# DIP2350.net
KiCad netlist of a schematic drawn in Altium Designer
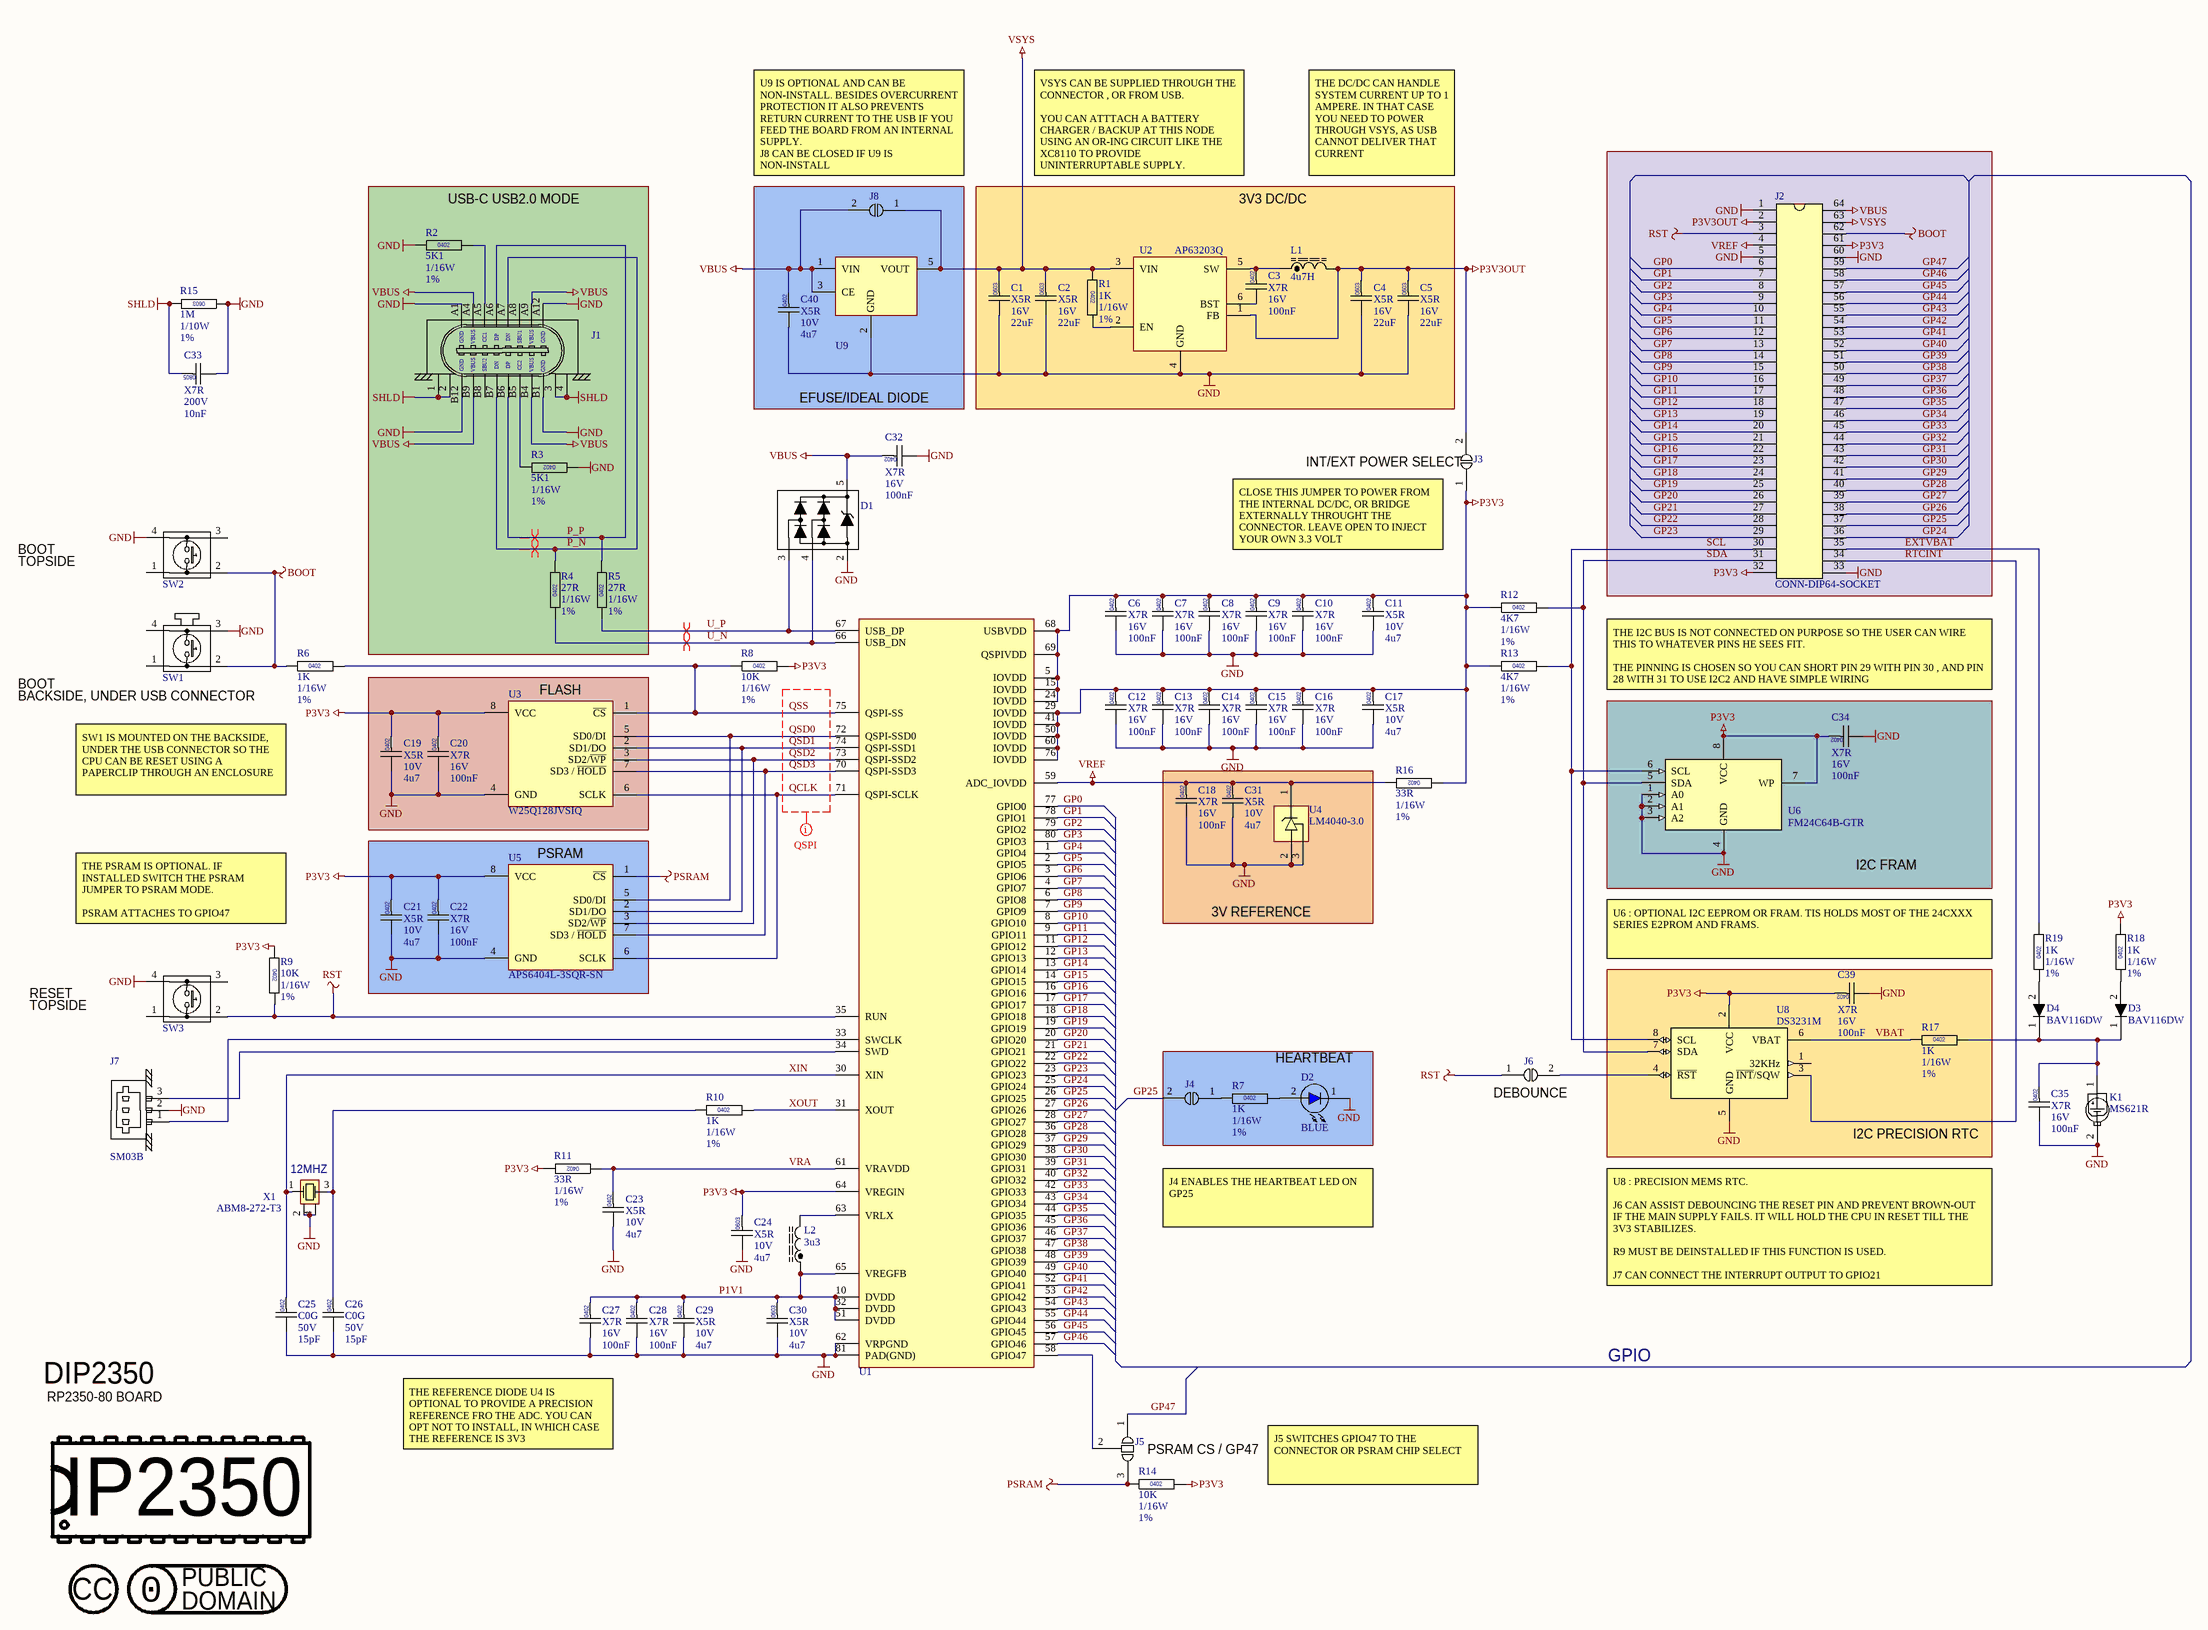
[diagram p0: DIP2350.SchDoc]

(export (version "E")
  (design (tool "Eeschema 10.0.6"))
  (components
    (comp (ref "C1")
      (value "CAP0603")
      (footprint "CAPC0603")
      (description "CAPACITOR,CERAMIC,22uF,16V,X5R,0603")
      (fields
        (field (name "DIELECTRIC") "X5R")
        (field (name "VOLTAGE") "16V")
        (field (name "CAPACITANCE") "22uF")
      )
      (libsource (lib "CAPACITORS") (part "CAPC-0603-22uF-16V-X5R"))
    )
    (comp (ref "C2")
      (value "CAP0603")
      (footprint "CAPC0603")
      (description "CAPACITOR,CERAMIC,22uF,16V,X5R,0603")
      (fields
        (field (name "DIELECTRIC") "X5R")
        (field (name "VOLTAGE") "16V")
        (field (name "CAPACITANCE") "22uF")
      )
      (libsource (lib "CAPACITORS") (part "CAPC-0603-22uF-16V-X5R"))
    )
    (comp (ref "C3")
      (value "CAP0402")
      (footprint "CAPC0402")
      (description "CAPACITOR,CERAMIC,100nF,16V,X7R,0402")
      (fields
        (field (name "DIELECTRIC") "X7R")
        (field (name "VOLTAGE") "16V")
        (field (name "CAPACITANCE") "100nF")
      )
      (libsource (lib "CAPACITORS") (part "CAPC-0402-100nF-16V-X7R"))
    )
    (comp (ref "C4")
      (value "CAP0603")
      (footprint "CAPC0603")
      (description "CAPACITOR,CERAMIC,22uF,16V,X5R,0603")
      (fields
        (field (name "DIELECTRIC") "X5R")
        (field (name "VOLTAGE") "16V")
        (field (name "CAPACITANCE") "22uF")
      )
      (libsource (lib "CAPACITORS") (part "CAPC-0603-22uF-16V-X5R"))
    )
    (comp (ref "C5")
      (value "CAP0603")
      (footprint "CAPC0603")
      (description "CAPACITOR,CERAMIC,22uF,16V,X5R,0603")
      (fields
        (field (name "DIELECTRIC") "X5R")
        (field (name "VOLTAGE") "16V")
        (field (name "CAPACITANCE") "22uF")
      )
      (libsource (lib "CAPACITORS") (part "CAPC-0603-22uF-16V-X5R"))
    )
    (comp (ref "C6")
      (value "CAP0402")
      (footprint "CAPC0402")
      (description "CAPACITOR,CERAMIC,100nF,16V,X7R,0402")
      (fields
        (field (name "DIELECTRIC") "X7R")
        (field (name "VOLTAGE") "16V")
        (field (name "CAPACITANCE") "100nF")
      )
      (libsource (lib "CAPACITORS") (part "CAPC-0402-100nF-16V-X7R"))
    )
    (comp (ref "C7")
      (value "CAP0402")
      (footprint "CAPC0402")
      (description "CAPACITOR,CERAMIC,100nF,16V,X7R,0402")
      (fields
        (field (name "DIELECTRIC") "X7R")
        (field (name "VOLTAGE") "16V")
        (field (name "CAPACITANCE") "100nF")
      )
      (libsource (lib "CAPACITORS") (part "CAPC-0402-100nF-16V-X7R"))
    )
    (comp (ref "C8")
      (value "CAP0402")
      (footprint "CAPC0402")
      (description "CAPACITOR,CERAMIC,100nF,16V,X7R,0402")
      (fields
        (field (name "DIELECTRIC") "X7R")
        (field (name "VOLTAGE") "16V")
        (field (name "CAPACITANCE") "100nF")
      )
      (libsource (lib "CAPACITORS") (part "CAPC-0402-100nF-16V-X7R"))
    )
    (comp (ref "C9")
      (value "CAP0402")
      (footprint "CAPC0402")
      (description "CAPACITOR,CERAMIC,100nF,16V,X7R,0402")
      (fields
        (field (name "DIELECTRIC") "X7R")
        (field (name "VOLTAGE") "16V")
        (field (name "CAPACITANCE") "100nF")
      )
      (libsource (lib "CAPACITORS") (part "CAPC-0402-100nF-16V-X7R"))
    )
    (comp (ref "C10")
      (value "CAP0402")
      (footprint "CAPC0402")
      (description "CAPACITOR,CERAMIC,100nF,16V,X7R,0402")
      (fields
        (field (name "DIELECTRIC") "X7R")
        (field (name "VOLTAGE") "16V")
        (field (name "CAPACITANCE") "100nF")
      )
      (libsource (lib "CAPACITORS") (part "CAPC-0402-100nF-16V-X7R"))
    )
    (comp (ref "C11")
      (value "CAP0402")
      (footprint "CAPC0402")
      (description "CAPACITOR,CERAMIC,4u7,10V,X5R,0402")
      (fields
        (field (name "DIELECTRIC") "X5R")
        (field (name "VOLTAGE") "10V")
        (field (name "CAPACITANCE") "4u7")
      )
      (libsource (lib "CAPACITORS") (part "CAPC-0402-4u7-10V-X5R"))
    )
    (comp (ref "C12")
      (value "CAP0402")
      (footprint "CAPC0402")
      (description "CAPACITOR,CERAMIC,100nF,16V,X7R,0402")
      (fields
        (field (name "DIELECTRIC") "X7R")
        (field (name "VOLTAGE") "16V")
        (field (name "CAPACITANCE") "100nF")
      )
      (libsource (lib "CAPACITORS") (part "CAPC-0402-100nF-16V-X7R"))
    )
    (comp (ref "C13")
      (value "CAP0402")
      (footprint "CAPC0402")
      (description "CAPACITOR,CERAMIC,100nF,16V,X7R,0402")
      (fields
        (field (name "DIELECTRIC") "X7R")
        (field (name "VOLTAGE") "16V")
        (field (name "CAPACITANCE") "100nF")
      )
      (libsource (lib "CAPACITORS") (part "CAPC-0402-100nF-16V-X7R"))
    )
    (comp (ref "C14")
      (value "CAP0402")
      (footprint "CAPC0402")
      (description "CAPACITOR,CERAMIC,100nF,16V,X7R,0402")
      (fields
        (field (name "DIELECTRIC") "X7R")
        (field (name "VOLTAGE") "16V")
        (field (name "CAPACITANCE") "100nF")
      )
      (libsource (lib "CAPACITORS") (part "CAPC-0402-100nF-16V-X7R"))
    )
    (comp (ref "C15")
      (value "CAP0402")
      (footprint "CAPC0402")
      (description "CAPACITOR,CERAMIC,100nF,16V,X7R,0402")
      (fields
        (field (name "DIELECTRIC") "X7R")
        (field (name "VOLTAGE") "16V")
        (field (name "CAPACITANCE") "100nF")
      )
      (libsource (lib "CAPACITORS") (part "CAPC-0402-100nF-16V-X7R"))
    )
    (comp (ref "C16")
      (value "CAP0402")
      (footprint "CAPC0402")
      (description "CAPACITOR,CERAMIC,100nF,16V,X7R,0402")
      (fields
        (field (name "DIELECTRIC") "X7R")
        (field (name "VOLTAGE") "16V")
        (field (name "CAPACITANCE") "100nF")
      )
      (libsource (lib "CAPACITORS") (part "CAPC-0402-100nF-16V-X7R"))
    )
    (comp (ref "C17")
      (value "CAP0402")
      (footprint "CAPC0402")
      (description "CAPACITOR,CERAMIC,4u7,10V,X5R,0402")
      (fields
        (field (name "DIELECTRIC") "X5R")
        (field (name "VOLTAGE") "10V")
        (field (name "CAPACITANCE") "4u7")
      )
      (libsource (lib "CAPACITORS") (part "CAPC-0402-4u7-10V-X5R"))
    )
    (comp (ref "C18")
      (value "CAP0402")
      (footprint "CAPC0402")
      (description "CAPACITOR,CERAMIC,100nF,16V,X7R,0402")
      (fields
        (field (name "DIELECTRIC") "X7R")
        (field (name "VOLTAGE") "16V")
        (field (name "CAPACITANCE") "100nF")
      )
      (libsource (lib "CAPACITORS") (part "CAPC-0402-100nF-16V-X7R"))
    )
    (comp (ref "C19")
      (value "CAP0402")
      (footprint "CAPC0402")
      (description "CAPACITOR,CERAMIC,4u7,10V,X5R,0402")
      (fields
        (field (name "DIELECTRIC") "X5R")
        (field (name "VOLTAGE") "10V")
        (field (name "CAPACITANCE") "4u7")
      )
      (libsource (lib "CAPACITORS") (part "CAPC-0402-4u7-10V-X5R"))
    )
    (comp (ref "C20")
      (value "CAP0402")
      (footprint "CAPC0402")
      (description "CAPACITOR,CERAMIC,100nF,16V,X7R,0402")
      (fields
        (field (name "DIELECTRIC") "X7R")
        (field (name "VOLTAGE") "16V")
        (field (name "CAPACITANCE") "100nF")
      )
      (libsource (lib "CAPACITORS") (part "CAPC-0402-100nF-16V-X7R"))
    )
    (comp (ref "C21")
      (value "CAP0402")
      (footprint "CAPC0402")
      (description "CAPACITOR,CERAMIC,4u7,10V,X5R,0402")
      (fields
        (field (name "DIELECTRIC") "X5R")
        (field (name "VOLTAGE") "10V")
        (field (name "CAPACITANCE") "4u7")
      )
      (libsource (lib "CAPACITORS") (part "CAPC-0402-4u7-10V-X5R"))
    )
    (comp (ref "C22")
      (value "CAP0402")
      (footprint "CAPC0402")
      (description "CAPACITOR,CERAMIC,100nF,16V,X7R,0402")
      (fields
        (field (name "DIELECTRIC") "X7R")
        (field (name "VOLTAGE") "16V")
        (field (name "CAPACITANCE") "100nF")
      )
      (libsource (lib "CAPACITORS") (part "CAPC-0402-100nF-16V-X7R"))
    )
    (comp (ref "C23")
      (value "CAP0402")
      (footprint "CAPC0402")
      (description "CAPACITOR,CERAMIC,4u7,10V,X5R,0402")
      (fields
        (field (name "DIELECTRIC") "X5R")
        (field (name "VOLTAGE") "10V")
        (field (name "CAPACITANCE") "4u7")
      )
      (libsource (lib "CAPACITORS") (part "CAPC-0402-4u7-10V-X5R"))
    )
    (comp (ref "C24")
      (value "CAP0603")
      (footprint "CAPC0603")
      (description "CAPACITOR,CERAMIC,4u7,10V,X5R,0603")
      (fields
        (field (name "DIELECTRIC") "X5R")
        (field (name "VOLTAGE") "10V")
        (field (name "CAPACITANCE") "4u7")
      )
      (libsource (lib "CAPACITORS") (part "CAPC-0603-4u7-10V-X5R"))
    )
    (comp (ref "C25")
      (value "CAP0603")
      (footprint "CAPC0402")
      (description "CAPACITOR,CERAMIC,15pF,50V,C0G,0402")
      (fields
        (field (name "DIELECTRIC") "C0G")
        (field (name "VOLTAGE") "50V")
        (field (name "CAPACITANCE") "15pF")
      )
      (libsource (lib "CAPACITORS") (part "CAPC-0402-15PF-50V-C0G"))
    )
    (comp (ref "C26")
      (value "CAP0603")
      (footprint "CAPC0402")
      (description "CAPACITOR,CERAMIC,15pF,50V,C0G,0402")
      (fields
        (field (name "DIELECTRIC") "C0G")
        (field (name "VOLTAGE") "50V")
        (field (name "CAPACITANCE") "15pF")
      )
      (libsource (lib "CAPACITORS") (part "CAPC-0402-15PF-50V-C0G"))
    )
    (comp (ref "C27")
      (value "CAP0402")
      (footprint "CAPC0402")
      (description "CAPACITOR,CERAMIC,100nF,16V,X7R,0402")
      (fields
        (field (name "DIELECTRIC") "X7R")
        (field (name "VOLTAGE") "16V")
        (field (name "CAPACITANCE") "100nF")
      )
      (libsource (lib "CAPACITORS") (part "CAPC-0402-100nF-16V-X7R"))
    )
    (comp (ref "C28")
      (value "CAP0402")
      (footprint "CAPC0402")
      (description "CAPACITOR,CERAMIC,100nF,16V,X7R,0402")
      (fields
        (field (name "DIELECTRIC") "X7R")
        (field (name "VOLTAGE") "16V")
        (field (name "CAPACITANCE") "100nF")
      )
      (libsource (lib "CAPACITORS") (part "CAPC-0402-100nF-16V-X7R"))
    )
    (comp (ref "C29")
      (value "CAP0402")
      (footprint "CAPC0402")
      (description "CAPACITOR,CERAMIC,4u7,10V,X5R,0402")
      (fields
        (field (name "DIELECTRIC") "X5R")
        (field (name "VOLTAGE") "10V")
        (field (name "CAPACITANCE") "4u7")
      )
      (libsource (lib "CAPACITORS") (part "CAPC-0402-4u7-10V-X5R"))
    )
    (comp (ref "C30")
      (value "CAP0603")
      (footprint "CAPC0603")
      (description "CAPACITOR,CERAMIC,4u7,10V,X5R,0603")
      (fields
        (field (name "DIELECTRIC") "X5R")
        (field (name "VOLTAGE") "10V")
        (field (name "CAPACITANCE") "4u7")
      )
      (libsource (lib "CAPACITORS") (part "CAPC-0603-4u7-10V-X5R"))
    )
    (comp (ref "C31")
      (value "CAP0402")
      (footprint "CAPC0402")
      (description "CAPACITOR,CERAMIC,4u7,10V,X5R,0402")
      (fields
        (field (name "DIELECTRIC") "X5R")
        (field (name "VOLTAGE") "10V")
        (field (name "CAPACITANCE") "4u7")
      )
      (libsource (lib "CAPACITORS") (part "CAPC-0402-4u7-10V-X5R"))
    )
    (comp (ref "C32")
      (value "CAP0402")
      (footprint "CAPC0402")
      (description "CAPACITOR,CERAMIC,100nF,16V,X7R,0402")
      (fields
        (field (name "DIELECTRIC") "X7R")
        (field (name "VOLTAGE") "16V")
        (field (name "CAPACITANCE") "100nF")
      )
      (libsource (lib "CAPACITORS") (part "CAPC-0402-100nF-16V-X7R"))
    )
    (comp (ref "C33")
      (value "CAP0805")
      (footprint "CAPC0805")
      (description "CAPACITOR,CERAMIC,10nF,200V,X7R,0805 (2012),ESD")
      (fields
        (field (name "DIELECTRIC") "X7R")
        (field (name "VOLTAGE") "200V")
        (field (name "CAPACITANCE") "10nF")
      )
      (libsource (lib "CAPACITORS") (part "CAPC-0805-10nF-200V-ESD"))
    )
    (comp (ref "C34")
      (value "CAP0402")
      (footprint "CAPC0402")
      (description "CAPACITOR,CERAMIC,100nF,16V,X7R,0402")
      (fields
        (field (name "DIELECTRIC") "X7R")
        (field (name "VOLTAGE") "16V")
        (field (name "CAPACITANCE") "100nF")
      )
      (libsource (lib "CAPACITORS") (part "CAPC-0402-100nF-16V-X7R"))
    )
    (comp (ref "C35")
      (value "CAP0402")
      (footprint "CAPC0402")
      (description "CAPACITOR,CERAMIC,100nF,16V,X7R,0402")
      (fields
        (field (name "DIELECTRIC") "X7R")
        (field (name "VOLTAGE") "16V")
        (field (name "CAPACITANCE") "100nF")
      )
      (libsource (lib "CAPACITORS") (part "CAPC-0402-100nF-16V-X7R"))
    )
    (comp (ref "C39")
      (value "CAP0402")
      (footprint "CAPC0402")
      (description "CAPACITOR,CERAMIC,100nF,16V,X7R,0402")
      (fields
        (field (name "DIELECTRIC") "X7R")
        (field (name "VOLTAGE") "16V")
        (field (name "CAPACITANCE") "100nF")
      )
      (libsource (lib "CAPACITORS") (part "CAPC-0402-100nF-16V-X7R"))
    )
    (comp (ref "C40")
      (value "CAP0402")
      (footprint "CAPC0402")
      (description "CAPACITOR,CERAMIC,4u7,10V,X5R,0402")
      (fields
        (field (name "DIELECTRIC") "X5R")
        (field (name "VOLTAGE") "10V")
        (field (name "CAPACITANCE") "4u7")
      )
      (libsource (lib "CAPACITORS") (part "CAPC-0402-4u7-10V-X5R"))
    )
    (comp (ref "D1")
      (value "TVS-WURTH-824011")
      (footprint "SOT23-5")
      (description "DIODE,TVS,DUAL,UNIDIRECTIONAL,USB")
      (libsource (lib "DIODES") (part "TVS-WURTH-824011"))
    )
    (comp (ref "D2")
      (value "BLUE")
      (footprint "LED-0603-BLUE")
      (description "LED,BLUE,0603")
      (libsource (lib "LED") (part "LED-WURTH-150060BS75000"))
    )
    (comp (ref "D3")
      (value "BAV116DW")
      (footprint "SOD323")
      (description "DIODE,75V,215mA,SOD323,LOW LEAKAGE")
      (libsource (lib "DIODES") (part "DIODE-DIODES-BAV116WS"))
    )
    (comp (ref "D4")
      (value "BAV116DW")
      (footprint "SOD323")
      (description "DIODE,75V,215mA,SOD323,LOW LEAKAGE")
      (libsource (lib "DIODES") (part "DIODE-DIODES-BAV116WS"))
    )
    (comp (ref "J1")
      (value "CONN-USBC-USB2-HOR")
      (footprint "CONN-GCT-USB4085")
      (description "CONN,USB-C,16P,RA,TH,8.94X9.17")
      (libsource (lib "CONNECTORS") (part "CONN-USBC-USB2-HOR"))
    )
    (comp (ref "J2")
      (value "CONN-DIP64-SOCKET")
      (footprint "CONN-DIP64-SOCKET")
      (libsource (lib "CONNECTORS") (part "CONN-DIP64-SOCKET"))
    )
    (comp (ref "J3")
      (value "SOLDERPAD-2")
      (footprint "SOLDERPAD-2")
      (libsource (lib "BOARDFEATURES") (part "SOLDERPAD-2"))
    )
    (comp (ref "J4")
      (value "SOLDERPAD-2")
      (footprint "SOLDERPAD-2")
      (libsource (lib "BOARDFEATURES") (part "SOLDERPAD-2"))
    )
    (comp (ref "J5")
      (value "SOLDERPAD-3")
      (footprint "SOLDERPAD-3")
      (libsource (lib "BOARDFEATURES") (part "SOLDERPAD-3"))
    )
    (comp (ref "J6")
      (value "SOLDERPAD-2")
      (footprint "SOLDERPAD-2")
      (libsource (lib "BOARDFEATURES") (part "SOLDERPAD-2"))
    )
    (comp (ref "J7")
      (value "SM03B")
      (footprint "CONN-JST-SM03B-SRSS-TB")
      (description "CONN,1X3,1MM,RA,SMD,JST,SM03B")
      (libsource (lib "CONNECTORS") (part "CONN-JST-SM03B-SRSS-TB"))
    )
    (comp (ref "J8")
      (value "SOLDERPAD-2")
      (footprint "SOLDERPAD-2")
      (libsource (lib "BOARDFEATURES") (part "SOLDERPAD-2"))
    )
    (comp (ref "K1")
      (value "MS621R")
      (footprint "BAT-SEIKO-MS621R")
      (description "BAT,3V,SMD,SEIKO MS621R")
      (libsource (lib "BATTERIES") (part "BAT-SEIKO-MS621R"))
    )
    (comp (ref "L1")
      (value "4u7H")
      (footprint "IND-ABRACON-ASPI-3012S-3R9N-T")
      (description "IND,4.7uH,1.06A,3X3, NRH3012T4R7MN")
      (fields (field (name "Comment") "4.7uH"))
      (libsource (lib "INDUCTORS") (part "IND-TAIYO-NRH3012T4R7MN"))
    )
    (comp (ref "L2")
      (value "3u3")
      (footprint "IND-ABRACON-B201610S3R3-101-T")
      (description "IND,3U3,RP2350, ABRACON AOTA-B201610S3R3-101-T")
      (fields (field (name "Comment") "AOTA-B201610S3R3-101-T"))
      (libsource (lib "INDUCTORS") (part "IND-ABRACON-AOTA-B201610S3R3-101-T"))
    )
    (comp (ref "LOGO1")
      (value "LOGO-LICENSE-CC0-PUBLIC")
      (footprint "LOGO-LICENSE-CC0-PUBLIC")
      (libsource (lib "LOGO") (part "LOGO-LICENSE-CC0-PUBLIC"))
    )
    (comp (ref "LOGO2")
      (value "LOGO-LICENSE-CC")
      (footprint "LOGO-LICENSE-CC")
      (libsource (lib "LOGO") (part "LOGO-LICENSE-CC"))
    )
    (comp (ref "R1")
      (value "1K")
      (footprint "RESC0402")
      (description "RESISTOR,1K,1%,63mW,0402 (1005)")
      (fields
        (field (name "POWER") "1/16W")
        (field (name "TOLERANCE") "1%")
        (field (name "Comment") "RESC0402")
      )
      (libsource (lib "RESISTORS") (part "RESC-0402-1K-1%-1/10W"))
    )
    (comp (ref "R2")
      (value "5K1")
      (footprint "RESC0402")
      (description "RESISTOR,5K1,1%,63mW,0402 (1005)")
      (fields
        (field (name "POWER") "1/16W")
        (field (name "TOLERANCE") "1%")
        (field (name "Comment") "RESC0402")
      )
      (libsource (lib "RESISTORS") (part "RESC-0402-5K1-1%-1/10W"))
    )
    (comp (ref "R3")
      (value "5K1")
      (footprint "RESC0402")
      (description "RESISTOR,5K1,1%,63mW,0402 (1005)")
      (fields
        (field (name "POWER") "1/16W")
        (field (name "TOLERANCE") "1%")
        (field (name "Comment") "RESC0402")
      )
      (libsource (lib "RESISTORS") (part "RESC-0402-5K1-1%-1/10W"))
    )
    (comp (ref "R4")
      (value "27R")
      (footprint "RESC0402")
      (description "RESISTOR,27R,1%,63mW,0402 (1005)")
      (fields
        (field (name "POWER") "1/16W")
        (field (name "TOLERANCE") "1%")
        (field (name "Comment") "RESC0402")
      )
      (libsource (lib "RESISTORS") (part "RESC-0402-27R-1%-1/10W"))
    )
    (comp (ref "R5")
      (value "27R")
      (footprint "RESC0402")
      (description "RESISTOR,27R,1%,63mW,0402 (1005)")
      (fields
        (field (name "POWER") "1/16W")
        (field (name "TOLERANCE") "1%")
        (field (name "Comment") "RESC0402")
      )
      (libsource (lib "RESISTORS") (part "RESC-0402-27R-1%-1/10W"))
    )
    (comp (ref "R6")
      (value "1K")
      (footprint "RESC0402")
      (description "RESISTOR,1K,1%,63mW,0402 (1005)")
      (fields
        (field (name "POWER") "1/16W")
        (field (name "TOLERANCE") "1%")
        (field (name "Comment") "RESC0402")
      )
      (libsource (lib "RESISTORS") (part "RESC-0402-1K-1%-1/10W"))
    )
    (comp (ref "R7")
      (value "1K")
      (footprint "RESC0402")
      (description "RESISTOR,1K,1%,63mW,0402 (1005)")
      (fields
        (field (name "POWER") "1/16W")
        (field (name "TOLERANCE") "1%")
        (field (name "Comment") "RESC0402")
      )
      (libsource (lib "RESISTORS") (part "RESC-0402-1K-1%-1/10W"))
    )
    (comp (ref "R8")
      (value "10K")
      (footprint "RESC0402")
      (description "RESISTOR,10K,1%,63mW,0402 (1005)")
      (fields
        (field (name "POWER") "1/16W")
        (field (name "TOLERANCE") "1%")
        (field (name "Comment") "RESC0402")
      )
      (libsource (lib "RESISTORS") (part "RESC-0402-10K-1%-1/10W"))
    )
    (comp (ref "R9")
      (value "10K")
      (footprint "RESC0402")
      (description "RESISTOR,10K,1%,63mW,0402 (1005)")
      (fields
        (field (name "POWER") "1/16W")
        (field (name "TOLERANCE") "1%")
        (field (name "Comment") "RESC0402")
      )
      (libsource (lib "RESISTORS") (part "RESC-0402-10K-1%-1/10W"))
    )
    (comp (ref "R10")
      (value "1K")
      (footprint "RESC0402")
      (description "RESISTOR,1K,1%,63mW,0402 (1005)")
      (fields
        (field (name "POWER") "1/16W")
        (field (name "TOLERANCE") "1%")
        (field (name "Comment") "RESC0402")
      )
      (libsource (lib "RESISTORS") (part "RESC-0402-1K-1%-1/10W"))
    )
    (comp (ref "R11")
      (value "33R")
      (footprint "RESC0402")
      (description "RESISTOR,33R,1%,63mW,0402 (1005)")
      (fields
        (field (name "POWER") "1/16W")
        (field (name "TOLERANCE") "1%")
        (field (name "Comment") "RESC0402")
      )
      (libsource (lib "RESISTORS") (part "RESC-0402-33R-1%-1/10W"))
    )
    (comp (ref "R12")
      (value "4K7")
      (footprint "RESC0402")
      (description "RESISTOR,4K7,1%,63mW,0402 (1005)")
      (fields
        (field (name "POWER") "1/16W")
        (field (name "TOLERANCE") "1%")
        (field (name "Comment") "RESC0402")
      )
      (libsource (lib "RESISTORS") (part "RESC-0402-4K7-1%-1/10W"))
    )
    (comp (ref "R13")
      (value "4K7")
      (footprint "RESC0402")
      (description "RESISTOR,4K7,1%,63mW,0402 (1005)")
      (fields
        (field (name "POWER") "1/16W")
        (field (name "TOLERANCE") "1%")
        (field (name "Comment") "RESC0402")
      )
      (libsource (lib "RESISTORS") (part "RESC-0402-4K7-1%-1/10W"))
    )
    (comp (ref "R14")
      (value "10K")
      (footprint "RESC0402")
      (description "RESISTOR,10K,1%,63mW,0402 (1005)")
      (fields
        (field (name "POWER") "1/16W")
        (field (name "TOLERANCE") "1%")
        (field (name "Comment") "RESC0402")
      )
      (libsource (lib "RESISTORS") (part "RESC-0402-10K-1%-1/10W"))
    )
    (comp (ref "R15")
      (value "1M")
      (footprint "RESC0603")
      (description "RESISTOR,1M,1%,100mW,0603 (1608)")
      (fields
        (field (name "POWER") "1/10W")
        (field (name "TOLERANCE") "1%")
        (field (name "Comment") "RESC0603")
      )
      (libsource (lib "RESISTORS") (part "RESC-0603-1M-1%-1/10W"))
    )
    (comp (ref "R16")
      (value "33R")
      (footprint "RESC0402")
      (description "RESISTOR,33R,1%,63mW,0402 (1005)")
      (fields
        (field (name "POWER") "1/16W")
        (field (name "TOLERANCE") "1%")
        (field (name "Comment") "RESC0402")
      )
      (libsource (lib "RESISTORS") (part "RESC-0402-33R-1%-1/10W"))
    )
    (comp (ref "R17")
      (value "1K")
      (footprint "RESC0402")
      (description "RESISTOR,1K,1%,63mW,0402 (1005)")
      (fields
        (field (name "POWER") "1/16W")
        (field (name "TOLERANCE") "1%")
        (field (name "Comment") "RESC0402")
      )
      (libsource (lib "RESISTORS") (part "RESC-0402-1K-1%-1/10W"))
    )
    (comp (ref "R18")
      (value "1K")
      (footprint "RESC0402")
      (description "RESISTOR,1K,1%,63mW,0402 (1005)")
      (fields
        (field (name "POWER") "1/16W")
        (field (name "TOLERANCE") "1%")
        (field (name "Comment") "RESC0402")
      )
      (libsource (lib "RESISTORS") (part "RESC-0402-1K-1%-1/10W"))
    )
    (comp (ref "R19")
      (value "1K")
      (footprint "RESC0402")
      (description "RESISTOR,1K,1%,63mW,0402 (1005)")
      (fields
        (field (name "POWER") "1/16W")
        (field (name "TOLERANCE") "1%")
        (field (name "Comment") "RESC0402")
      )
      (libsource (lib "RESISTORS") (part "RESC-0402-1K-1%-1/10W"))
    )
    (comp (ref "SW1")
      (value "SWITCH-E-SWITCH-TL1016")
      (footprint "SWITCH-ESWITCH-TL1016")
      (description "SW,SMD,TACT,4PIN,2.9X3.5,4PIN,SIDE ACTUATOR")
      (libsource (lib "SWITCH") (part "SWITCH-E-SWITCH-TL1016"))
    )
    (comp (ref "SW2")
      (value "SWITCH-PANASONIC-EVP-AA202K")
      (footprint "SWITCH-PANASONIC-EVP-AA202K")
      (description "SW,SMD,TACT,4PIN,2.9X3.5,4PIN")
      (libsource (lib "SWITCH") (part "SWITCH-PANASONIC-EVP-AA202K"))
    )
    (comp (ref "SW3")
      (value "SWITCH-PANASONIC-EVP-AA202K")
      (footprint "SWITCH-PANASONIC-EVP-AA202K")
      (description "SW,SMD,TACT,4PIN,2.9X3.5,4PIN")
      (libsource (lib "SWITCH") (part "SWITCH-PANASONIC-EVP-AA202K"))
    )
    (comp (ref "U1")
      (value "IC-RP2350-DIP64")
      (footprint "QFN40P1000X1000X90_HS-81N")
      (description "IC,CPU,RP2350B,QFN80")
      (libsource (lib "IC-CPU") (part "IC-RP2350-DIP64"))
    )
    (comp (ref "U2")
      (value "AP63203Q")
      (footprint "SOT23-6")
      (description "IC,PMIC,STEP-DOWN, 2A 3.3V")
      (libsource (lib "IC-REG") (part "IC-DIODES-AP63203Q"))
    )
    (comp (ref "U3")
      (value "W25Q128JVSIQ")
      (footprint "SO127P790-8N")
      (description "IC,FLASH,QSPI,16Mx8")
      (libsource (lib "IC-SPI") (part "IC-WINBOND-W25Q128JVSIQ"))
    )
    (comp (ref "U4")
      (value "LM4040-3.0")
      (footprint "SOT23")
      (description "IC,VOLTAGE REFERENCE,3.0V")
      (libsource (lib "IC-REG") (part "IC-TI-LM4040-3"))
    )
    (comp (ref "U5")
      (value "APS6404L-3SQR-SN")
      (footprint "SO127P600-8N")
      (description "IC,PSRAM,QSPI,8Mx8,SO8")
      (libsource (lib "IC-SPI") (part "IC-APMEMORY-APS6404L-3SQR-SN"))
    )
    (comp (ref "U6")
      (value "FM24C64B-GTR")
      (footprint "SO127P600-8N")
      (description "IC,FRAM,I2C, 64KBIT")
      (libsource (lib "IC-I2C") (part "IC-INFINEON-FM24C64B-GTR"))
    )
    (comp (ref "U8")
      (value "DS3231M")
      (footprint "SO127P600-8N")
      (description "IC,RTC,I2C,DS3231M")
      (libsource (lib "IC-I2C") (part "IC-ANALOG-DS3231M"))
    )
    (comp (ref "U9")
      (value "XC8110")
      (footprint "SOT23-5")
      (description "IC,PMIC,IDEAL DIODE ORING CONTROLLER")
      (libsource (lib "IC-REG") (part "IC-TOREX-XC8110"))
    )
    (comp (ref "X1")
      (value "ABM8-272-T3")
      (footprint "XTAL-ABRACON-ABM8-272-T3")
      (description "XTAL,12MHZ,RP2350")
      (libsource (lib "CRYSTALS") (part "XTAL-ABRACON-ABM8-272-T3"))
    )
  )
  (nets
    (net (code "1") (name "/EXTVBAT") (class "Default")
      (node (ref "J2") (pin "35") (pinfunction "35_35") (pintype "passive"))
      (node (ref "R19") (pin "2") (pintype "passive"))
    )
    (net (code "2") (name "/GP0") (class "Default")
      (node (ref "J2") (pin "6") (pinfunction "6_6") (pintype "passive"))
      (node (ref "U1") (pin "77") (pinfunction "GPIO0_77") (pintype "passive"))
    )
    (net (code "3") (name "/GP1") (class "Default")
      (node (ref "J2") (pin "7") (pinfunction "7_7") (pintype "passive"))
      (node (ref "U1") (pin "78") (pinfunction "GPIO1_78") (pintype "passive"))
    )
    (net (code "4") (name "/GP2") (class "Default")
      (node (ref "J2") (pin "8") (pinfunction "8_8") (pintype "passive"))
      (node (ref "U1") (pin "79") (pinfunction "GPIO2_79") (pintype "passive"))
    )
    (net (code "5") (name "/GP3") (class "Default")
      (node (ref "J2") (pin "9") (pinfunction "9_9") (pintype "passive"))
      (node (ref "U1") (pin "80") (pinfunction "GPIO3_80") (pintype "passive"))
    )
    (net (code "6") (name "/GP4") (class "Default")
      (node (ref "J2") (pin "10") (pinfunction "10_10") (pintype "passive"))
      (node (ref "U1") (pin "1") (pinfunction "GPIO4_1") (pintype "passive"))
    )
    (net (code "7") (name "/GP5") (class "Default")
      (node (ref "J2") (pin "11") (pinfunction "11_11") (pintype "passive"))
      (node (ref "U1") (pin "2") (pinfunction "GPIO5_2") (pintype "passive"))
    )
    (net (code "8") (name "/GP6") (class "Default")
      (node (ref "J2") (pin "12") (pinfunction "12_12") (pintype "passive"))
      (node (ref "U1") (pin "3") (pinfunction "GPIO6_3") (pintype "passive"))
    )
    (net (code "9") (name "/GP7") (class "Default")
      (node (ref "J2") (pin "13") (pinfunction "13_13") (pintype "passive"))
      (node (ref "U1") (pin "4") (pinfunction "GPIO7_4") (pintype "passive"))
    )
    (net (code "10") (name "/GP8") (class "Default")
      (node (ref "J2") (pin "14") (pinfunction "14_14") (pintype "passive"))
      (node (ref "U1") (pin "6") (pinfunction "GPIO8_6") (pintype "passive"))
    )
    (net (code "11") (name "/GP9") (class "Default")
      (node (ref "J2") (pin "15") (pinfunction "15_15") (pintype "passive"))
      (node (ref "U1") (pin "7") (pinfunction "GPIO9_7") (pintype "passive"))
    )
    (net (code "12") (name "/GP10") (class "Default")
      (node (ref "J2") (pin "16") (pinfunction "16_16") (pintype "passive"))
      (node (ref "U1") (pin "8") (pinfunction "GPIO10_8") (pintype "passive"))
    )
    (net (code "13") (name "/GP11") (class "Default")
      (node (ref "J2") (pin "17") (pinfunction "17_17") (pintype "passive"))
      (node (ref "U1") (pin "9") (pinfunction "GPIO11_9") (pintype "passive"))
    )
    (net (code "14") (name "/GP12") (class "Default")
      (node (ref "J2") (pin "18") (pinfunction "18_18") (pintype "passive"))
      (node (ref "U1") (pin "11") (pinfunction "GPIO12_11") (pintype "passive"))
    )
    (net (code "15") (name "/GP13") (class "Default")
      (node (ref "J2") (pin "19") (pinfunction "19_19") (pintype "passive"))
      (node (ref "U1") (pin "12") (pinfunction "GPIO13_12") (pintype "passive"))
    )
    (net (code "16") (name "/GP14") (class "Default")
      (node (ref "J2") (pin "20") (pinfunction "20_20") (pintype "passive"))
      (node (ref "U1") (pin "13") (pinfunction "GPIO14_13") (pintype "passive"))
    )
    (net (code "17") (name "/GP15") (class "Default")
      (node (ref "J2") (pin "21") (pinfunction "21_21") (pintype "passive"))
      (node (ref "U1") (pin "14") (pinfunction "GPIO15_14") (pintype "passive"))
    )
    (net (code "18") (name "/GP16") (class "Default")
      (node (ref "J2") (pin "22") (pinfunction "22_22") (pintype "passive"))
      (node (ref "U1") (pin "16") (pinfunction "GPIO16_16") (pintype "passive"))
    )
    (net (code "19") (name "/GP17") (class "Default")
      (node (ref "J2") (pin "23") (pinfunction "23_23") (pintype "passive"))
      (node (ref "U1") (pin "17") (pinfunction "GPIO17_17") (pintype "passive"))
    )
    (net (code "20") (name "/GP18") (class "Default")
      (node (ref "J2") (pin "24") (pinfunction "24_24") (pintype "passive"))
      (node (ref "U1") (pin "18") (pinfunction "GPIO18_18") (pintype "passive"))
    )
    (net (code "21") (name "/GP19") (class "Default")
      (node (ref "J2") (pin "25") (pinfunction "25_25") (pintype "passive"))
      (node (ref "U1") (pin "19") (pinfunction "GPIO19_19") (pintype "passive"))
    )
    (net (code "22") (name "/GP20") (class "Default")
      (node (ref "J2") (pin "26") (pinfunction "26_26") (pintype "passive"))
      (node (ref "U1") (pin "20") (pinfunction "GPIO20_20") (pintype "passive"))
    )
    (net (code "23") (name "/GP21") (class "Default")
      (node (ref "J2") (pin "27") (pinfunction "27_27") (pintype "passive"))
      (node (ref "U1") (pin "21") (pinfunction "GPIO21_21") (pintype "passive"))
    )
    (net (code "24") (name "/GP22") (class "Default")
      (node (ref "J2") (pin "28") (pinfunction "28_28") (pintype "passive"))
      (node (ref "U1") (pin "22") (pinfunction "GPIO22_22") (pintype "passive"))
    )
    (net (code "25") (name "/GP23") (class "Default")
      (node (ref "J2") (pin "29") (pinfunction "29_29") (pintype "passive"))
      (node (ref "U1") (pin "23") (pinfunction "GPIO23_23") (pintype "passive"))
    )
    (net (code "26") (name "/GP24") (class "Default")
      (node (ref "J2") (pin "36") (pinfunction "36_36") (pintype "passive"))
      (node (ref "U1") (pin "25") (pinfunction "GPIO24_25") (pintype "passive"))
    )
    (net (code "27") (name "/GP25") (class "Default")
      (node (ref "J2") (pin "37") (pinfunction "37_37") (pintype "passive"))
      (node (ref "J4") (pin "2") (pinfunction "2_2") (pintype "passive"))
      (node (ref "U1") (pin "26") (pinfunction "GPIO25_26") (pintype "passive"))
    )
    (net (code "28") (name "/GP26") (class "Default")
      (node (ref "J2") (pin "38") (pinfunction "38_38") (pintype "passive"))
      (node (ref "U1") (pin "27") (pinfunction "GPIO26_27") (pintype "passive"))
    )
    (net (code "29") (name "/GP27") (class "Default")
      (node (ref "J2") (pin "39") (pinfunction "39_39") (pintype "passive"))
      (node (ref "U1") (pin "28") (pinfunction "GPIO27_28") (pintype "passive"))
    )
    (net (code "30") (name "/GP28") (class "Default")
      (node (ref "J2") (pin "40") (pinfunction "40_40") (pintype "passive"))
      (node (ref "U1") (pin "36") (pinfunction "GPIO28_36") (pintype "passive"))
    )
    (net (code "31") (name "/GP29") (class "Default")
      (node (ref "J2") (pin "41") (pinfunction "33_41") (pintype "passive"))
      (node (ref "U1") (pin "37") (pinfunction "GPIO29_37") (pintype "passive"))
    )
    (net (code "32") (name "/GP30") (class "Default")
      (node (ref "J2") (pin "42") (pinfunction "34_42") (pintype "passive"))
      (node (ref "U1") (pin "38") (pinfunction "GPIO30_38") (pintype "passive"))
    )
    (net (code "33") (name "/GP31") (class "Default")
      (node (ref "J2") (pin "43") (pinfunction "35_43") (pintype "passive"))
      (node (ref "U1") (pin "39") (pinfunction "GPIO31_39") (pintype "passive"))
    )
    (net (code "34") (name "/GP32") (class "Default")
      (node (ref "J2") (pin "44") (pinfunction "36_44") (pintype "passive"))
      (node (ref "U1") (pin "40") (pinfunction "GPIO32_40") (pintype "passive"))
    )
    (net (code "35") (name "/GP33") (class "Default")
      (node (ref "J2") (pin "45") (pinfunction "37_45") (pintype "passive"))
      (node (ref "U1") (pin "42") (pinfunction "GPIO33_42") (pintype "passive"))
    )
    (net (code "36") (name "/GP34") (class "Default")
      (node (ref "J2") (pin "46") (pinfunction "38_46") (pintype "passive"))
      (node (ref "U1") (pin "43") (pinfunction "GPIO34_43") (pintype "passive"))
    )
    (net (code "37") (name "/GP35") (class "Default")
      (node (ref "J2") (pin "47") (pinfunction "39_47") (pintype "passive"))
      (node (ref "U1") (pin "44") (pinfunction "GPIO35_44") (pintype "passive"))
    )
    (net (code "38") (name "/GP36") (class "Default")
      (node (ref "J2") (pin "48") (pinfunction "40_48") (pintype "passive"))
      (node (ref "U1") (pin "45") (pinfunction "GPIO36_45") (pintype "passive"))
    )
    (net (code "39") (name "/GP37") (class "Default")
      (node (ref "J2") (pin "49") (pinfunction "33_49") (pintype "passive"))
      (node (ref "U1") (pin "46") (pinfunction "GPIO37_46") (pintype "passive"))
    )
    (net (code "40") (name "/GP38") (class "Default")
      (node (ref "J2") (pin "50") (pinfunction "34_50") (pintype "passive"))
      (node (ref "U1") (pin "47") (pinfunction "GPIO38_47") (pintype "passive"))
    )
    (net (code "41") (name "/GP39") (class "Default")
      (node (ref "J2") (pin "51") (pinfunction "35_51") (pintype "passive"))
      (node (ref "U1") (pin "48") (pinfunction "GPIO39_48") (pintype "passive"))
    )
    (net (code "42") (name "/GP40") (class "Default")
      (node (ref "J2") (pin "52") (pinfunction "36_52") (pintype "passive"))
      (node (ref "U1") (pin "49") (pinfunction "GPIO40_49") (pintype "passive"))
    )
    (net (code "43") (name "/GP41") (class "Default")
      (node (ref "J2") (pin "53") (pinfunction "37_53") (pintype "passive"))
      (node (ref "U1") (pin "52") (pinfunction "GPIO41_52") (pintype "passive"))
    )
    (net (code "44") (name "/GP42") (class "Default")
      (node (ref "J2") (pin "54") (pinfunction "38_54") (pintype "passive"))
      (node (ref "U1") (pin "53") (pinfunction "GPIO42_53") (pintype "passive"))
    )
    (net (code "45") (name "/GP43") (class "Default")
      (node (ref "J2") (pin "55") (pinfunction "39_55") (pintype "passive"))
      (node (ref "U1") (pin "54") (pinfunction "GPIO43_54") (pintype "passive"))
    )
    (net (code "46") (name "/GP44") (class "Default")
      (node (ref "J2") (pin "56") (pinfunction "40_56") (pintype "passive"))
      (node (ref "U1") (pin "55") (pinfunction "GPIO44_55") (pintype "passive"))
    )
    (net (code "47") (name "/GP45") (class "Default")
      (node (ref "J2") (pin "57") (pinfunction "33_57") (pintype "passive"))
      (node (ref "U1") (pin "56") (pinfunction "GPIO45_56") (pintype "passive"))
    )
    (net (code "48") (name "/GP46") (class "Default")
      (node (ref "J2") (pin "58") (pinfunction "34_58") (pintype "passive"))
      (node (ref "U1") (pin "57") (pinfunction "GPIO46_57") (pintype "passive"))
    )
    (net (code "49") (name "/GP47") (class "Default")
      (node (ref "J2") (pin "59") (pinfunction "35_59") (pintype "passive"))
      (node (ref "J5") (pin "1") (pinfunction "1_1") (pintype "passive"))
    )
    (net (code "50") (name "/P1V1") (class "Default")
      (node (ref "C27") (pin "1") (pintype "passive"))
      (node (ref "C28") (pin "1") (pintype "passive"))
      (node (ref "C29") (pin "1") (pintype "passive"))
      (node (ref "C30") (pin "1") (pintype "passive"))
      (node (ref "L2") (pin "1") (pinfunction "1_1") (pintype "passive"))
      (node (ref "U1") (pin "10") (pinfunction "DVDD_10") (pintype "passive"))
      (node (ref "U1") (pin "32") (pinfunction "DVDD_32") (pintype "passive"))
      (node (ref "U1") (pin "51") (pinfunction "DVDD_51") (pintype "passive"))
      (node (ref "U1") (pin "65") (pinfunction "VREGFB_65") (pintype "passive"))
    )
    (net (code "51") (name "/P_N") (class "Default")
      (node (ref "J1") (pin "A7") (pinfunction "A7_A7") (pintype "passive"))
      (node (ref "J1") (pin "B7") (pinfunction "B7_B7") (pintype "passive"))
      (node (ref "R4") (pin "1") (pintype "passive"))
    )
    (net (code "52") (name "/P_P") (class "Default")
      (node (ref "J1") (pin "A6") (pinfunction "A6_A6") (pintype "passive"))
      (node (ref "J1") (pin "B6") (pinfunction "B6_B6") (pintype "passive"))
      (node (ref "R5") (pin "1") (pintype "passive"))
    )
    (net (code "53") (name "/QCLK") (class "Default")
      (node (ref "U1") (pin "71") (pinfunction "QSPI-SCLK_71") (pintype "passive"))
      (node (ref "U3") (pin "6") (pinfunction "SCLK_6") (pintype "passive"))
      (node (ref "U5") (pin "6") (pinfunction "SCLK_6") (pintype "passive"))
    )
    (net (code "54") (name "/QSD0") (class "Default")
      (node (ref "U1") (pin "72") (pinfunction "QSPI-SSD0_72") (pintype "passive"))
      (node (ref "U3") (pin "5") (pinfunction "SD0/DI_5") (pintype "passive"))
      (node (ref "U5") (pin "5") (pinfunction "SD0/DI_5") (pintype "passive"))
    )
    (net (code "55") (name "/QSD1") (class "Default")
      (node (ref "U1") (pin "74") (pinfunction "QSPI-SSD1_74") (pintype "passive"))
      (node (ref "U3") (pin "2") (pinfunction "SD1/DO_2") (pintype "passive"))
      (node (ref "U5") (pin "2") (pinfunction "SD1/DO_2") (pintype "passive"))
    )
    (net (code "56") (name "/QSD2") (class "Default")
      (node (ref "U1") (pin "73") (pinfunction "QSPI-SSD2_73") (pintype "passive"))
      (node (ref "U3") (pin "3") (pinfunction "SD2/~{WP}_3") (pintype "passive"))
      (node (ref "U5") (pin "3") (pinfunction "SD2/~{WP}_3") (pintype "passive"))
    )
    (net (code "57") (name "/QSD3") (class "Default")
      (node (ref "U1") (pin "70") (pinfunction "QSPI-SSD3_70") (pintype "passive"))
      (node (ref "U3") (pin "7") (pinfunction "SD3_/_~{HOLD}_7") (pintype "passive"))
      (node (ref "U5") (pin "7") (pinfunction "SD3_/_~{HOLD}_7") (pintype "passive"))
    )
    (net (code "58") (name "/QSS") (class "Default")
      (node (ref "R6") (pin "2") (pintype "passive"))
      (node (ref "R8") (pin "1") (pintype "passive"))
      (node (ref "U1") (pin "75") (pinfunction "QSPI-SS_75") (pintype "passive"))
      (node (ref "U3") (pin "1") (pinfunction "~{CS}_1") (pintype "passive"))
    )
    (net (code "59") (name "/RTCINT") (class "Default")
      (node (ref "J2") (pin "34") (pinfunction "34_34") (pintype "passive"))
      (node (ref "U8") (pin "3") (pinfunction "~{INT}/SQW_3") (pintype "output"))
    )
    (net (code "60") (name "/SCL") (class "Default")
      (node (ref "J2") (pin "30") (pinfunction "30_30") (pintype "passive"))
      (node (ref "R13") (pin "2") (pintype "passive"))
      (node (ref "U6") (pin "6") (pinfunction "SCL_6") (pintype "input"))
      (node (ref "U8") (pin "8") (pinfunction "SCL_8") (pintype "bidirectional"))
    )
    (net (code "61") (name "/SDA") (class "Default")
      (node (ref "J2") (pin "31") (pinfunction "31_31") (pintype "passive"))
      (node (ref "R12") (pin "2") (pintype "passive"))
      (node (ref "U6") (pin "5") (pinfunction "SDA_5") (pintype "open_collector"))
      (node (ref "U8") (pin "7") (pinfunction "SDA_7") (pintype "bidirectional"))
    )
    (net (code "62") (name "/U_N") (class "Default")
      (node (ref "D1") (pin "4") (pinfunction "A_4") (pintype "passive"))
      (node (ref "R4") (pin "2") (pintype "passive"))
      (node (ref "U1") (pin "66") (pinfunction "USB_DN_66") (pintype "passive"))
    )
    (net (code "63") (name "/U_P") (class "Default")
      (node (ref "D1") (pin "3") (pinfunction "A_3") (pintype "passive"))
      (node (ref "R5") (pin "2") (pintype "passive"))
      (node (ref "U1") (pin "67") (pinfunction "USB_DP_67") (pintype "passive"))
    )
    (net (code "64") (name "/VBAT") (class "Default")
      (node (ref "R17") (pin "1") (pintype "passive"))
      (node (ref "U8") (pin "6") (pinfunction "VBAT_6") (pintype "passive"))
    )
    (net (code "65") (name "/VRA") (class "Default")
      (node (ref "C23") (pin "1") (pintype "passive"))
      (node (ref "R11") (pin "2") (pintype "passive"))
      (node (ref "U1") (pin "61") (pinfunction "VRAVDD_61") (pintype "passive"))
    )
    (net (code "66") (name "/XIN") (class "Default")
      (node (ref "C25") (pin "1") (pintype "passive"))
      (node (ref "U1") (pin "30") (pinfunction "XIN_30") (pintype "passive"))
      (node (ref "X1") (pin "1") (pinfunction "1_1") (pintype "passive"))
    )
    (net (code "67") (name "/XOUT") (class "Default")
      (node (ref "R10") (pin "2") (pintype "passive"))
      (node (ref "U1") (pin "31") (pinfunction "XOUT_31") (pintype "passive"))
    )
    (net (code "68") (name "BOOT") (class "Default")
      (node (ref "J2") (pin "62") (pinfunction "38_62") (pintype "passive"))
      (node (ref "R6") (pin "1") (pintype "passive"))
      (node (ref "SW1") (pin "2") (pinfunction "2_2") (pintype "passive"))
      (node (ref "SW2") (pin "2") (pinfunction "2_2") (pintype "passive"))
    )
    (net (code "69") (name "GND") (class "Default")
      (node (ref "C1") (pin "2") (pintype "passive"))
      (node (ref "C10") (pin "2") (pintype "passive"))
      (node (ref "C11") (pin "2") (pintype "passive"))
      (node (ref "C12") (pin "2") (pintype "passive"))
      (node (ref "C13") (pin "2") (pintype "passive"))
      (node (ref "C14") (pin "2") (pintype "passive"))
      (node (ref "C15") (pin "2") (pintype "passive"))
      (node (ref "C16") (pin "2") (pintype "passive"))
      (node (ref "C17") (pin "2") (pintype "passive"))
      (node (ref "C18") (pin "2") (pintype "passive"))
      (node (ref "C19") (pin "2") (pintype "passive"))
      (node (ref "C2") (pin "2") (pintype "passive"))
      (node (ref "C20") (pin "2") (pintype "passive"))
      (node (ref "C21") (pin "2") (pintype "passive"))
      (node (ref "C22") (pin "2") (pintype "passive"))
      (node (ref "C23") (pin "2") (pintype "passive"))
      (node (ref "C24") (pin "2") (pintype "passive"))
      (node (ref "C25") (pin "2") (pintype "passive"))
      (node (ref "C26") (pin "2") (pintype "passive"))
      (node (ref "C27") (pin "2") (pintype "passive"))
      (node (ref "C28") (pin "2") (pintype "passive"))
      (node (ref "C29") (pin "2") (pintype "passive"))
      (node (ref "C30") (pin "2") (pintype "passive"))
      (node (ref "C31") (pin "2") (pintype "passive"))
      (node (ref "C32") (pin "2") (pintype "passive"))
      (node (ref "C33") (pin "2") (pintype "passive"))
      (node (ref "C34") (pin "2") (pintype "passive"))
      (node (ref "C35") (pin "2") (pintype "passive"))
      (node (ref "C39") (pin "2") (pintype "passive"))
      (node (ref "C4") (pin "2") (pintype "passive"))
      (node (ref "C40") (pin "2") (pintype "passive"))
      (node (ref "C5") (pin "2") (pintype "passive"))
      (node (ref "C6") (pin "2") (pintype "passive"))
      (node (ref "C7") (pin "2") (pintype "passive"))
      (node (ref "C8") (pin "2") (pintype "passive"))
      (node (ref "C9") (pin "2") (pintype "passive"))
      (node (ref "D1") (pin "2") (pinfunction "A_2") (pintype "passive"))
      (node (ref "D2") (pin "1") (pinfunction "A_1") (pintype "passive"))
      (node (ref "J1") (pin "A1") (pinfunction "A1_A1") (pintype "passive"))
      (node (ref "J1") (pin "A12") (pinfunction "A12_A12") (pintype "passive"))
      (node (ref "J1") (pin "B1") (pinfunction "B1_B1") (pintype "passive"))
      (node (ref "J1") (pin "B12") (pinfunction "B12_B12") (pintype "passive"))
      (node (ref "J2") (pin "1") (pinfunction "1_1") (pintype "passive"))
      (node (ref "J2") (pin "33") (pinfunction "33_33") (pintype "passive"))
      (node (ref "J2") (pin "5") (pinfunction "5_5") (pintype "passive"))
      (node (ref "J2") (pin "60") (pinfunction "36_60") (pintype "passive"))
      (node (ref "J7") (pin "2") (pinfunction "2_2") (pintype "passive"))
      (node (ref "K1") (pin "2") (pinfunction "-_2") (pintype "passive"))
      (node (ref "R15") (pin "2") (pintype "passive"))
      (node (ref "R2") (pin "2") (pintype "passive"))
      (node (ref "R3") (pin "2") (pintype "passive"))
      (node (ref "SW1") (pin "3") (pinfunction "3_3") (pintype "passive"))
      (node (ref "SW2") (pin "4") (pinfunction "4_4") (pintype "passive"))
      (node (ref "SW3") (pin "4") (pinfunction "4_4") (pintype "passive"))
      (node (ref "U1") (pin "62") (pinfunction "VRPGND_62") (pintype "passive"))
      (node (ref "U1") (pin "81") (pinfunction "PAD(GND)_81") (pintype "passive"))
      (node (ref "U2") (pin "4") (pinfunction "GND_4") (pintype "passive"))
      (node (ref "U3") (pin "4") (pinfunction "GND_4") (pintype "passive"))
      (node (ref "U4") (pin "2") (pinfunction "2_2") (pintype "passive"))
      (node (ref "U4") (pin "3") (pinfunction "3_3") (pintype "passive"))
      (node (ref "U5") (pin "4") (pinfunction "GND_4") (pintype "passive"))
      (node (ref "U6") (pin "1") (pinfunction "A0_1") (pintype "input"))
      (node (ref "U6") (pin "2") (pinfunction "A1_2") (pintype "input"))
      (node (ref "U6") (pin "3") (pinfunction "A2_3") (pintype "input"))
      (node (ref "U6") (pin "4") (pinfunction "GND_4") (pintype "power_in"))
      (node (ref "U8") (pin "5") (pinfunction "GND_5") (pintype "power_in"))
      (node (ref "U9") (pin "2") (pinfunction "GND_2") (pintype "passive"))
      (node (ref "X1") (pin "2") (pinfunction "2_2") (pintype "passive"))
      (node (ref "X1") (pin "4") (pinfunction "4_4") (pintype "passive"))
    )
    (net (code "70") (name "Net-(C26-Pad1)") (class "Default")
      (node (ref "C26") (pin "1") (pintype "passive"))
      (node (ref "R10") (pin "1") (pintype "passive"))
      (node (ref "X1") (pin "3") (pinfunction "3_3") (pintype "passive"))
    )
    (net (code "71") (name "Net-(D2-K)") (class "Default")
      (node (ref "D2") (pin "2") (pinfunction "K_2") (pintype "passive"))
      (node (ref "R7") (pin "2") (pintype "passive"))
    )
    (net (code "72") (name "Net-(D3-A)") (class "Default")
      (node (ref "D3") (pin "2") (pinfunction "A_2") (pintype "passive"))
      (node (ref "R18") (pin "1") (pintype "passive"))
    )
    (net (code "73") (name "Net-(D3-K)") (class "Default")
      (node (ref "C35") (pin "1") (pintype "passive"))
      (node (ref "D3") (pin "1") (pinfunction "K_1") (pintype "passive"))
      (node (ref "D4") (pin "1") (pinfunction "K_1") (pintype "passive"))
      (node (ref "K1") (pin "1") (pinfunction "+_1") (pintype "passive"))
      (node (ref "R17") (pin "2") (pintype "passive"))
    )
    (net (code "74") (name "Net-(D4-A)") (class "Default")
      (node (ref "D4") (pin "2") (pinfunction "A_2") (pintype "passive"))
      (node (ref "R19") (pin "1") (pintype "passive"))
    )
    (net (code "75") (name "Net-(J1-PadA5)") (class "Default")
      (node (ref "J1") (pin "A5") (pinfunction "A5_A5") (pintype "passive"))
      (node (ref "R2") (pin "1") (pintype "passive"))
    )
    (net (code "76") (name "Net-(J1-PadB5)") (class "Default")
      (node (ref "J1") (pin "B5") (pinfunction "B5_B5") (pintype "passive"))
      (node (ref "R3") (pin "1") (pintype "passive"))
    )
    (net (code "77") (name "Net-(J4-Pad1)") (class "Default")
      (node (ref "J4") (pin "1") (pinfunction "1_1") (pintype "passive"))
      (node (ref "R7") (pin "1") (pintype "passive"))
    )
    (net (code "78") (name "Net-(U1-GPIO47)") (class "Default")
      (node (ref "J5") (pin "2") (pinfunction "2_2") (pintype "passive"))
      (node (ref "U1") (pin "58") (pinfunction "GPIO47_58") (pintype "passive"))
    )
    (net (code "79") (name "Net-(U1-SWCLK)") (class "Default")
      (node (ref "J7") (pin "1") (pinfunction "1_1") (pintype "passive"))
      (node (ref "U1") (pin "33") (pinfunction "SWCLK_33") (pintype "passive"))
    )
    (net (code "80") (name "Net-(U1-SWD)") (class "Default")
      (node (ref "J7") (pin "3") (pinfunction "3_3") (pintype "passive"))
      (node (ref "U1") (pin "34") (pinfunction "SWD_34") (pintype "passive"))
    )
    (net (code "81") (name "Net-(U1-VRLX)") (class "Default")
      (node (ref "L2") (pin "2") (pinfunction "2_2") (pintype "passive"))
      (node (ref "U1") (pin "63") (pinfunction "VRLX_63") (pintype "passive"))
    )
    (net (code "82") (name "Net-(U2-BST)") (class "Default")
      (node (ref "C3") (pin "2") (pintype "passive"))
      (node (ref "U2") (pin "6") (pinfunction "BST_6") (pintype "passive"))
    )
    (net (code "83") (name "Net-(U2-EN)") (class "Default")
      (node (ref "R1") (pin "1") (pintype "passive"))
      (node (ref "U2") (pin "2") (pinfunction "EN_2") (pintype "passive"))
    )
    (net (code "84") (name "Net-(U2-SW)") (class "Default")
      (node (ref "C3") (pin "1") (pintype "passive"))
      (node (ref "L1") (pin "1") (pinfunction "1_1") (pintype "passive"))
      (node (ref "U2") (pin "5") (pinfunction "SW_5") (pintype "passive"))
    )
    (net (code "85") (name "Net-(U8-~{RST})") (class "Default")
      (node (ref "J6") (pin "2") (pinfunction "2_2") (pintype "passive"))
      (node (ref "U8") (pin "4") (pinfunction "~{RST}_4") (pintype "bidirectional"))
    )
    (net (code "86") (name "P3V3") (class "Default")
      (node (ref "C10") (pin "1") (pintype "passive"))
      (node (ref "C11") (pin "1") (pintype "passive"))
      (node (ref "C12") (pin "1") (pintype "passive"))
      (node (ref "C13") (pin "1") (pintype "passive"))
      (node (ref "C14") (pin "1") (pintype "passive"))
      (node (ref "C15") (pin "1") (pintype "passive"))
      (node (ref "C16") (pin "1") (pintype "passive"))
      (node (ref "C17") (pin "1") (pintype "passive"))
      (node (ref "C19") (pin "1") (pintype "passive"))
      (node (ref "C20") (pin "1") (pintype "passive"))
      (node (ref "C21") (pin "1") (pintype "passive"))
      (node (ref "C22") (pin "1") (pintype "passive"))
      (node (ref "C24") (pin "1") (pintype "passive"))
      (node (ref "C34") (pin "1") (pintype "passive"))
      (node (ref "C39") (pin "1") (pintype "passive"))
      (node (ref "C6") (pin "1") (pintype "passive"))
      (node (ref "C7") (pin "1") (pintype "passive"))
      (node (ref "C8") (pin "1") (pintype "passive"))
      (node (ref "C9") (pin "1") (pintype "passive"))
      (node (ref "J2") (pin "32") (pinfunction "32_32") (pintype "passive"))
      (node (ref "J2") (pin "61") (pinfunction "37_61") (pintype "passive"))
      (node (ref "J3") (pin "1") (pinfunction "1_1") (pintype "passive"))
      (node (ref "R11") (pin "1") (pintype "passive"))
      (node (ref "R12") (pin "1") (pintype "passive"))
      (node (ref "R13") (pin "1") (pintype "passive"))
      (node (ref "R14") (pin "2") (pintype "passive"))
      (node (ref "R16") (pin "2") (pintype "passive"))
      (node (ref "R18") (pin "2") (pintype "passive"))
      (node (ref "R8") (pin "2") (pintype "passive"))
      (node (ref "R9") (pin "2") (pintype "passive"))
      (node (ref "U1") (pin "15") (pinfunction "IOVDD_15") (pintype "passive"))
      (node (ref "U1") (pin "24") (pinfunction "IOVDD_24") (pintype "passive"))
      (node (ref "U1") (pin "29") (pinfunction "IOVDD_29") (pintype "passive"))
      (node (ref "U1") (pin "41") (pinfunction "IOVDD_41") (pintype "passive"))
      (node (ref "U1") (pin "5") (pinfunction "IOVDD_5") (pintype "passive"))
      (node (ref "U1") (pin "50") (pinfunction "IOVDD_50") (pintype "passive"))
      (node (ref "U1") (pin "60") (pinfunction "IOVDD_60") (pintype "passive"))
      (node (ref "U1") (pin "64") (pinfunction "VREGIN_64") (pintype "passive"))
      (node (ref "U1") (pin "68") (pinfunction "USBVDD_68") (pintype "passive"))
      (node (ref "U1") (pin "69") (pinfunction "QSPIVDD_69") (pintype "passive"))
      (node (ref "U1") (pin "76") (pinfunction "IOVDD_76") (pintype "passive"))
      (node (ref "U3") (pin "8") (pinfunction "VCC_8") (pintype "passive"))
      (node (ref "U5") (pin "8") (pinfunction "VCC_8") (pintype "passive"))
      (node (ref "U6") (pin "7") (pinfunction "WP_7") (pintype "passive"))
      (node (ref "U6") (pin "8") (pinfunction "VCC_8") (pintype "passive"))
      (node (ref "U8") (pin "2") (pinfunction "VCC_2") (pintype "passive"))
    )
    (net (code "87") (name "P3V3OUT") (class "Default")
      (node (ref "C4") (pin "1") (pintype "passive"))
      (node (ref "C5") (pin "1") (pintype "passive"))
      (node (ref "J2") (pin "2") (pinfunction "2_2") (pintype "passive"))
      (node (ref "J3") (pin "2") (pinfunction "2_2") (pintype "passive"))
      (node (ref "L1") (pin "2") (pinfunction "2_2") (pintype "passive"))
      (node (ref "U2") (pin "1") (pinfunction "FB_1") (pintype "passive"))
    )
    (net (code "88") (name "PSRAM") (class "Default")
      (node (ref "J5") (pin "3") (pinfunction "3_3") (pintype "passive"))
      (node (ref "R14") (pin "1") (pintype "passive"))
      (node (ref "U5") (pin "1") (pinfunction "~{CS}_1") (pintype "passive"))
    )
    (net (code "89") (name "RST") (class "Default")
      (node (ref "J2") (pin "3") (pinfunction "3_3") (pintype "passive"))
      (node (ref "J6") (pin "1") (pinfunction "1_1") (pintype "passive"))
      (node (ref "R9") (pin "1") (pintype "passive"))
      (node (ref "SW3") (pin "2") (pinfunction "2_2") (pintype "passive"))
      (node (ref "U1") (pin "35") (pinfunction "RUN_35") (pintype "passive"))
    )
    (net (code "90") (name "SHLD") (class "Default")
      (node (ref "C33") (pin "1") (pintype "passive"))
      (node (ref "J1") (pin "1") (pinfunction "1_1") (pintype "passive"))
      (node (ref "J1") (pin "2") (pinfunction "2_2") (pintype "passive"))
      (node (ref "J1") (pin "3") (pinfunction "3_3") (pintype "passive"))
      (node (ref "J1") (pin "4") (pinfunction "4_4") (pintype "passive"))
      (node (ref "R15") (pin "1") (pintype "passive"))
    )
    (net (code "91") (name "VBUS") (class "Default")
      (node (ref "C32") (pin "1") (pintype "passive"))
      (node (ref "C40") (pin "1") (pintype "passive"))
      (node (ref "D1") (pin "5") (pinfunction "A_5") (pintype "passive"))
      (node (ref "J1") (pin "A4") (pinfunction "A4_A4") (pintype "passive"))
      (node (ref "J1") (pin "A9") (pinfunction "A9_A9") (pintype "passive"))
      (node (ref "J1") (pin "B4") (pinfunction "B4_B4") (pintype "passive"))
      (node (ref "J1") (pin "B9") (pinfunction "B9_B9") (pintype "passive"))
      (node (ref "J2") (pin "64") (pinfunction "40_64") (pintype "passive"))
      (node (ref "J8") (pin "2") (pinfunction "2_2") (pintype "passive"))
      (node (ref "U9") (pin "1") (pinfunction "VIN_1") (pintype "passive"))
      (node (ref "U9") (pin "3") (pinfunction "CE_3") (pintype "passive"))
    )
    (net (code "92") (name "VREF") (class "Default")
      (node (ref "C18") (pin "1") (pintype "passive"))
      (node (ref "C31") (pin "1") (pintype "passive"))
      (node (ref "J2") (pin "4") (pinfunction "4_4") (pintype "passive"))
      (node (ref "R16") (pin "1") (pintype "passive"))
      (node (ref "U1") (pin "59") (pinfunction "ADC_IOVDD_59") (pintype "passive"))
      (node (ref "U4") (pin "1") (pinfunction "1_1") (pintype "passive"))
    )
    (net (code "93") (name "VSYS") (class "Default")
      (node (ref "C1") (pin "1") (pintype "passive"))
      (node (ref "C2") (pin "1") (pintype "passive"))
      (node (ref "J2") (pin "63") (pinfunction "39_63") (pintype "passive"))
      (node (ref "J8") (pin "1") (pinfunction "1_1") (pintype "passive"))
      (node (ref "R1") (pin "2") (pintype "passive"))
      (node (ref "U2") (pin "3") (pinfunction "VIN_3") (pintype "passive"))
      (node (ref "U9") (pin "5") (pinfunction "VOUT_5") (pintype "passive"))
    )
    (net (code "94") (name "unconnected-(J1-PadA8)") (class "Default")
      (node (ref "J1") (pin "A8") (pinfunction "A8_A8") (pintype "passive"))
    )
    (net (code "95") (name "unconnected-(J1-PadB8)") (class "Default")
      (node (ref "J1") (pin "B8") (pinfunction "B8_B8") (pintype "passive"))
    )
    (net (code "96") (name "unconnected-(SW1-Pad1)") (class "Default")
      (node (ref "SW1") (pin "1") (pinfunction "1_1") (pintype "passive"))
    )
    (net (code "97") (name "unconnected-(SW1-Pad4)") (class "Default")
      (node (ref "SW1") (pin "4") (pinfunction "4_4") (pintype "passive"))
    )
    (net (code "98") (name "unconnected-(SW2-Pad1)") (class "Default")
      (node (ref "SW2") (pin "1") (pinfunction "1_1") (pintype "passive"))
    )
    (net (code "99") (name "unconnected-(SW2-Pad3)") (class "Default")
      (node (ref "SW2") (pin "3") (pinfunction "3_3") (pintype "passive"))
    )
    (net (code "100") (name "unconnected-(SW3-Pad1)") (class "Default")
      (node (ref "SW3") (pin "1") (pinfunction "1_1") (pintype "passive"))
    )
    (net (code "101") (name "unconnected-(SW3-Pad3)") (class "Default")
      (node (ref "SW3") (pin "3") (pinfunction "3_3") (pintype "passive"))
    )
    (net (code "102") (name "unconnected-(U8-32KHz-Pad1)") (class "Default")
      (node (ref "U8") (pin "1") (pinfunction "32KHz_1") (pintype "output"))
    )
  )
)
